# mbedshield041.net
KiCad netlist of a schematic drawn in EAGLE
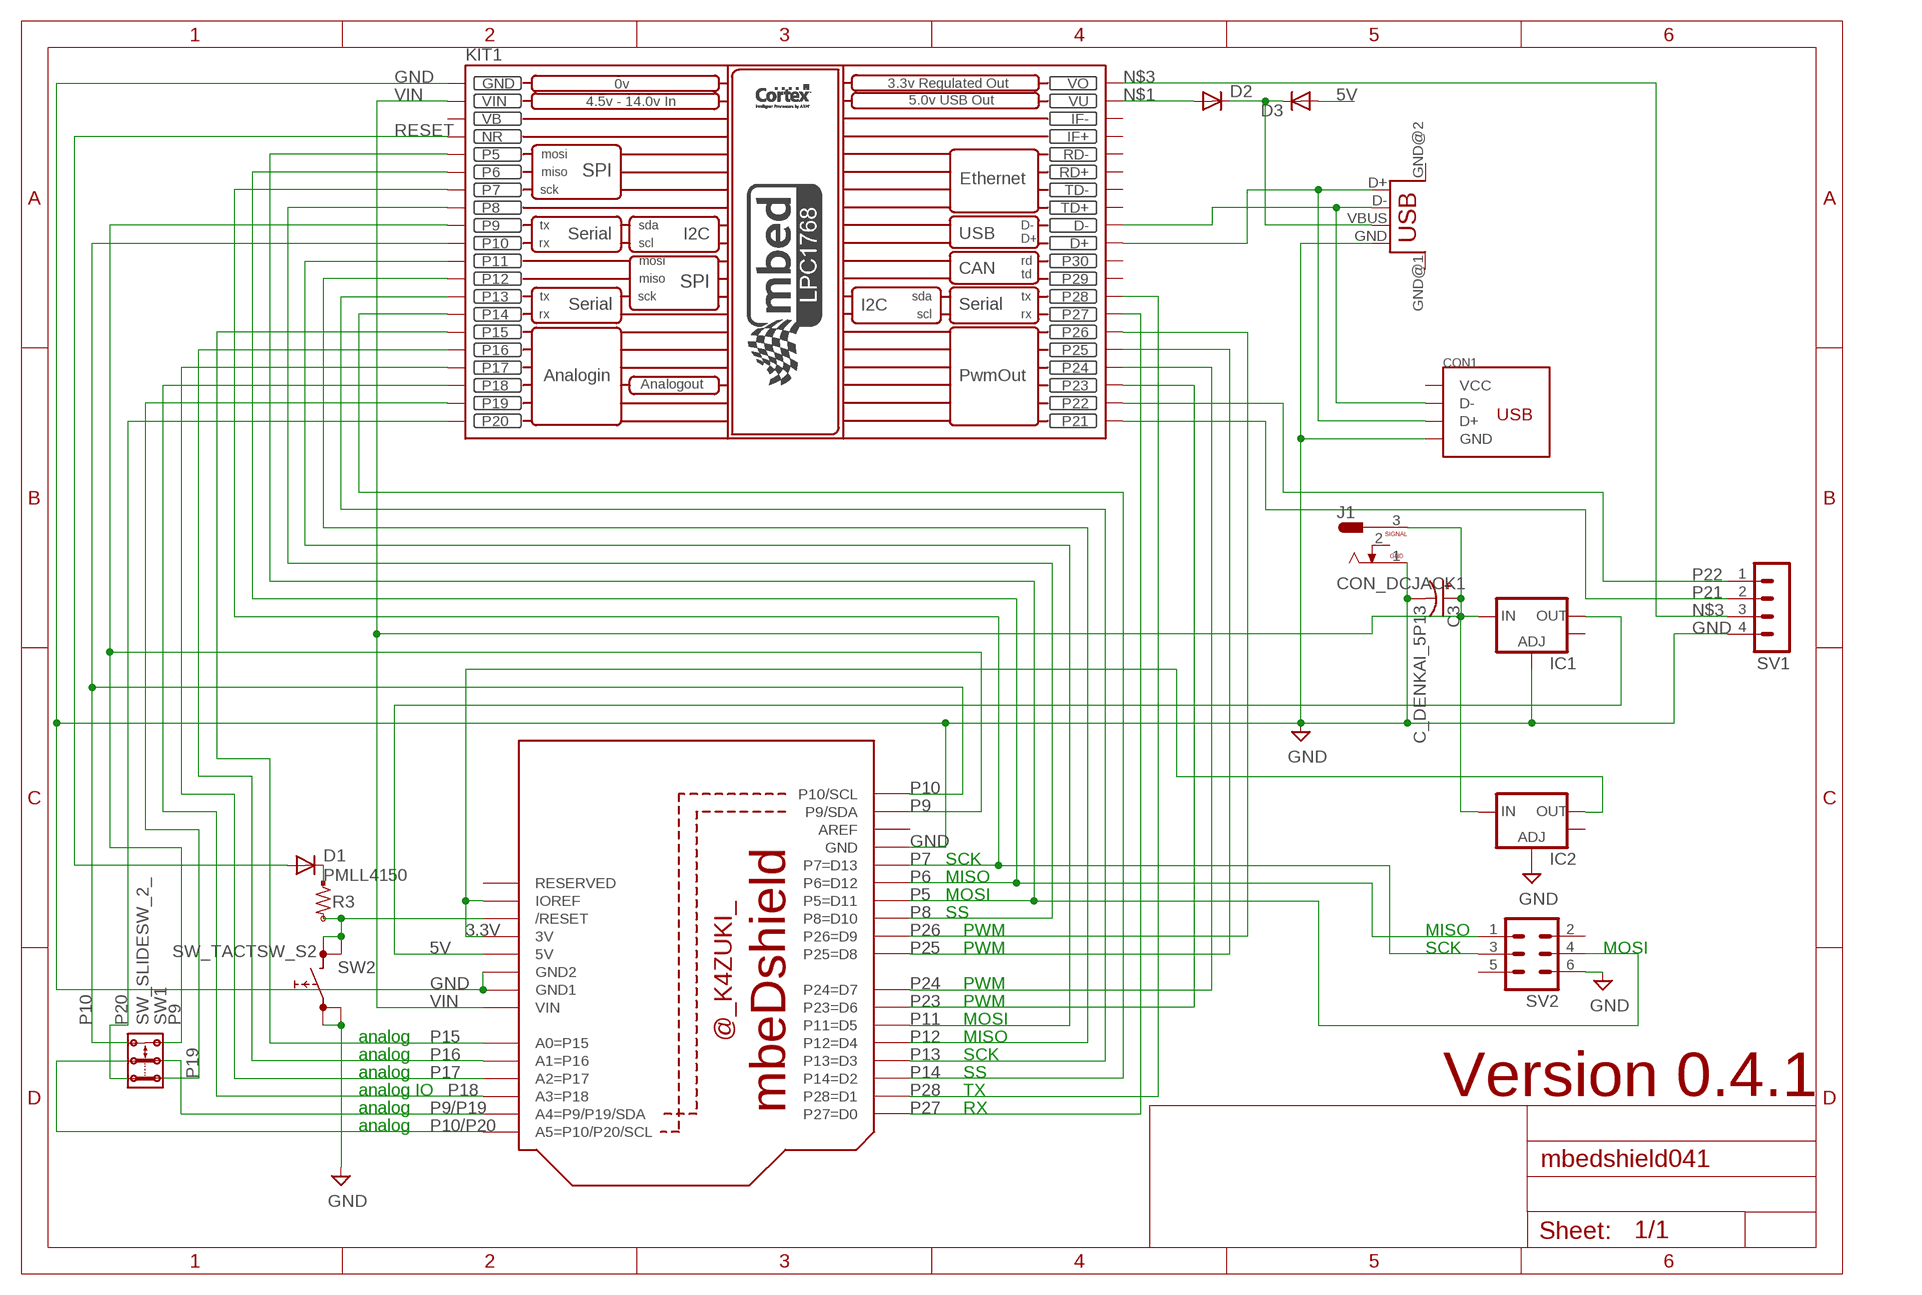
[diagram p0: schematic, sheet 1]

(export (version "E")
  (design (tool "Eeschema 10.0.6"))
  (components
    (comp (ref "C3")
      (value "C_DENKAI_5P13")
      (footprint "eagle-import:153CLV-1014")
      (libsource (lib "eagle-import") (part "CPOL-US153CLV-1014"))
    )
    (comp (ref "CON1")
      (value "CON_USB")
      (footprint "eagle-import:CON_USB_MINIB_AKI")
      (libsource (lib "eagle-import") (part "CON_USB"))
    )
    (comp (ref "D1")
      (value "PMLL4150")
      (footprint "eagle-import:SOD80C")
      (libsource (lib "eagle-import") (part "PMLL4150"))
    )
    (comp (ref "D2")
      (value "PMLL4150")
      (footprint "eagle-import:SOD80C")
      (libsource (lib "eagle-import") (part "PMLL4150"))
    )
    (comp (ref "D3")
      (value "PMLL4150")
      (footprint "eagle-import:SOD80C")
      (libsource (lib "eagle-import") (part "PMLL4150"))
    )
    (comp (ref "IC1")
      (value "V_REG_LM1117SOT223")
      (footprint "eagle-import:SOT223")
      (libsource (lib "eagle-import") (part "V_REG_LM1117SOT223"))
    )
    (comp (ref "IC2")
      (value "V_REG_LM1117SOT223")
      (footprint "eagle-import:SOT223")
      (libsource (lib "eagle-import") (part "V_REG_LM1117SOT223"))
    )
    (comp (ref "J1")
      (value "CON_DCJACK1")
      (footprint "eagle-import:CON_DCJACK")
      (libsource (lib "eagle-import") (part "CON_DCJACK1"))
    )
    (comp (ref "KIT1")
      (value "MBED_NXP_LPC1768")
      (footprint "eagle-import:MBED-KIT")
      (libsource (lib "eagle-import") (part "MBED_NXP_LPC1768"))
    )
    (comp (ref "R3")
      (value "R_US_PAD_VIA_2125")
      (footprint "eagle-import:R_2125_PADVIA")
      (libsource (lib "eagle-import") (part "R_US_PAD_VIA_2125"))
    )
    (comp (ref "SV1")
      (value "MA04-1")
      (footprint "eagle-import:MA04-1")
      (libsource (lib "eagle-import") (part "MA04-1"))
    )
    (comp (ref "SV2")
      (value "MA03-2")
      (footprint "eagle-import:MA03-2")
      (libsource (lib "eagle-import") (part "MA03-2"))
    )
    (comp (ref "SW1")
      (value "SW_SLIDESW_2_")
      (footprint "eagle-import:SW_SLIDE_2X2_1")
      (libsource (lib "eagle-import") (part "SW_SLIDESW_2_"))
    )
    (comp (ref "SW2")
      (value "SW_TACTSW_S2")
      (footprint "eagle-import:SW_TACTSW_B3F-10XX")
      (libsource (lib "eagle-import") (part "SW_TACTSW_S2"))
    )
    (comp (ref "U$1")
      (value "BOARD_MBEDSHIELD")
      (footprint "eagle-import:BOARD_MBEDSHIOELD")
      (libsource (lib "eagle-import") (part "BOARD_MBEDSHIELD"))
    )
    (comp (ref "USB")
      (value "USB")
      (footprint "eagle-import:USB-FEMALE-A-PTH")
      (libsource (lib "eagle-import") (part "USB"))
    )
  )
  (nets
    (net (code "1") (name "/3.3V") (class "Default")
      (node (ref "IC2") (pin "2") (pinfunction "OUT_2") (pintype "output"))
      (node (ref "U$1") (pin "3V") (pinfunction "3V_3V") (pintype "power_in"))
      (node (ref "U$1") (pin "IOREF") (pinfunction "IOREF_IOREF") (pintype "output"))
    )
    (net (code "2") (name "/5V") (class "Default")
      (node (ref "D3") (pin "A") (pinfunction "A_A") (pintype "passive"))
      (node (ref "IC1") (pin "2") (pinfunction "OUT_2") (pintype "output"))
      (node (ref "U$1") (pin "5V") (pinfunction "5V_5V") (pintype "power_in"))
    )
    (net (code "3") (name "/N$1") (class "Default")
      (node (ref "D2") (pin "A") (pinfunction "A_A") (pintype "passive"))
      (node (ref "KIT1") (pin "VU") (pinfunction "VU_VU") (pintype "power_in"))
    )
    (net (code "4") (name "/N$3") (class "Default")
      (node (ref "KIT1") (pin "VOUT") (pinfunction "VO_VOUT") (pintype "power_in"))
      (node (ref "SV1") (pin "3") (pinfunction "3_3") (pintype "passive"))
    )
    (net (code "5") (name "/P5") (class "Default")
      (node (ref "KIT1") (pin "P$5") (pinfunction "P5_P$5") (pintype "bidirectional"))
      (node (ref "SV2") (pin "4") (pinfunction "4_4") (pintype "passive"))
      (node (ref "U$1") (pin "D11") (pinfunction "P5=D11_D11") (pintype "bidirectional"))
    )
    (net (code "6") (name "/P6") (class "Default")
      (node (ref "KIT1") (pin "P$6") (pinfunction "P6_P$6") (pintype "bidirectional"))
      (node (ref "SV2") (pin "1") (pinfunction "1_1") (pintype "passive"))
      (node (ref "U$1") (pin "D12") (pinfunction "P6=D12_D12") (pintype "bidirectional"))
    )
    (net (code "7") (name "/P7") (class "Default")
      (node (ref "KIT1") (pin "P$7") (pinfunction "P7_P$7") (pintype "bidirectional"))
      (node (ref "SV2") (pin "3") (pinfunction "3_3") (pintype "passive"))
      (node (ref "U$1") (pin "D13") (pinfunction "P7=D13_D13") (pintype "bidirectional"))
    )
    (net (code "8") (name "/P8") (class "Default")
      (node (ref "KIT1") (pin "P$8") (pinfunction "P8_P$8") (pintype "bidirectional"))
      (node (ref "U$1") (pin "D10") (pinfunction "P8=D10_D10") (pintype "bidirectional"))
    )
    (net (code "9") (name "/P9") (class "Default")
      (node (ref "KIT1") (pin "P$9") (pinfunction "P9_P$9") (pintype "bidirectional"))
      (node (ref "SW1") (pin "2.1") (pinfunction "2.1_2.1") (pintype "passive"))
      (node (ref "U$1") (pin "SDA") (pinfunction "P9/SDA_SDA") (pintype "bidirectional"))
    )
    (net (code "10") (name "/P9{slash}P19") (class "Default")
      (node (ref "SW1") (pin "COM.1") (pinfunction "COM.1_COM.1") (pintype "passive"))
      (node (ref "U$1") (pin "A4") (pinfunction "A4=P9/P19/SDA_A4") (pintype "bidirectional"))
    )
    (net (code "11") (name "/P10") (class "Default")
      (node (ref "KIT1") (pin "P$10") (pinfunction "P10_P$10") (pintype "bidirectional"))
      (node (ref "SW1") (pin "2.2") (pinfunction "2.2_2.2") (pintype "passive"))
      (node (ref "U$1") (pin "SCL") (pinfunction "P10/SCL_SCL") (pintype "bidirectional"))
    )
    (net (code "12") (name "/P10{slash}P20") (class "Default")
      (node (ref "SW1") (pin "COM.2") (pinfunction "COM.2_COM.2") (pintype "passive"))
      (node (ref "U$1") (pin "A5") (pinfunction "A5=P10/P20/SCL_A5") (pintype "bidirectional"))
    )
    (net (code "13") (name "/P11") (class "Default")
      (node (ref "KIT1") (pin "P$11") (pinfunction "P11_P$11") (pintype "bidirectional"))
      (node (ref "U$1") (pin "D5") (pinfunction "P11=D5_D5") (pintype "bidirectional"))
    )
    (net (code "14") (name "/P12") (class "Default")
      (node (ref "KIT1") (pin "P$12") (pinfunction "P12_P$12") (pintype "bidirectional"))
      (node (ref "U$1") (pin "D4") (pinfunction "P12=D4_D4") (pintype "bidirectional"))
    )
    (net (code "15") (name "/P13") (class "Default")
      (node (ref "KIT1") (pin "P$13") (pinfunction "P13_P$13") (pintype "bidirectional"))
      (node (ref "U$1") (pin "D3") (pinfunction "P13=D3_D3") (pintype "bidirectional"))
    )
    (net (code "16") (name "/P14") (class "Default")
      (node (ref "KIT1") (pin "P$14") (pinfunction "P14_P$14") (pintype "bidirectional"))
      (node (ref "U$1") (pin "D2") (pinfunction "P14=D2_D2") (pintype "bidirectional"))
    )
    (net (code "17") (name "/P15") (class "Default")
      (node (ref "KIT1") (pin "P$15") (pinfunction "P15_P$15") (pintype "bidirectional"))
      (node (ref "U$1") (pin "A0") (pinfunction "A0=P15_A0") (pintype "bidirectional"))
    )
    (net (code "18") (name "/P16") (class "Default")
      (node (ref "KIT1") (pin "P$16") (pinfunction "P16_P$16") (pintype "bidirectional"))
      (node (ref "U$1") (pin "A1") (pinfunction "A1=P16_A1") (pintype "bidirectional"))
    )
    (net (code "19") (name "/P17") (class "Default")
      (node (ref "KIT1") (pin "P$17") (pinfunction "P17_P$17") (pintype "bidirectional"))
      (node (ref "U$1") (pin "A2") (pinfunction "A2=P17_A2") (pintype "bidirectional"))
    )
    (net (code "20") (name "/P18") (class "Default")
      (node (ref "KIT1") (pin "P$18") (pinfunction "P18_P$18") (pintype "bidirectional"))
      (node (ref "U$1") (pin "A3") (pinfunction "A3=P18_A3") (pintype "bidirectional"))
    )
    (net (code "21") (name "/P19") (class "Default")
      (node (ref "KIT1") (pin "P$19") (pinfunction "P19_P$19") (pintype "bidirectional"))
      (node (ref "SW1") (pin "1.1") (pinfunction "1.1_1.1") (pintype "passive"))
    )
    (net (code "22") (name "/P20") (class "Default")
      (node (ref "KIT1") (pin "P$20") (pinfunction "P20_P$20") (pintype "bidirectional"))
      (node (ref "SW1") (pin "1.2") (pinfunction "1.2_1.2") (pintype "passive"))
    )
    (net (code "23") (name "/P21") (class "Default")
      (node (ref "KIT1") (pin "P$21") (pinfunction "P21_P$21") (pintype "bidirectional"))
      (node (ref "SV1") (pin "2") (pinfunction "2_2") (pintype "passive"))
    )
    (net (code "24") (name "/P22") (class "Default")
      (node (ref "KIT1") (pin "P$22") (pinfunction "P22_P$22") (pintype "bidirectional"))
      (node (ref "SV1") (pin "1") (pinfunction "1_1") (pintype "passive"))
    )
    (net (code "25") (name "/P23") (class "Default")
      (node (ref "KIT1") (pin "P$23") (pinfunction "P23_P$23") (pintype "bidirectional"))
      (node (ref "U$1") (pin "D6") (pinfunction "P23=D6_D6") (pintype "bidirectional"))
    )
    (net (code "26") (name "/P24") (class "Default")
      (node (ref "KIT1") (pin "P$24") (pinfunction "P24_P$24") (pintype "bidirectional"))
      (node (ref "U$1") (pin "D7") (pinfunction "P24=D7_D7") (pintype "bidirectional"))
    )
    (net (code "27") (name "/P25") (class "Default")
      (node (ref "KIT1") (pin "P$25") (pinfunction "P25_P$25") (pintype "bidirectional"))
      (node (ref "U$1") (pin "D8") (pinfunction "P25=D8_D8") (pintype "bidirectional"))
    )
    (net (code "28") (name "/P26") (class "Default")
      (node (ref "KIT1") (pin "P$26") (pinfunction "P26_P$26") (pintype "bidirectional"))
      (node (ref "U$1") (pin "D9") (pinfunction "P26=D9_D9") (pintype "bidirectional"))
    )
    (net (code "29") (name "/P27") (class "Default")
      (node (ref "KIT1") (pin "P$27") (pinfunction "P27_P$27") (pintype "bidirectional"))
      (node (ref "U$1") (pin "D0") (pinfunction "P27=D0_D0") (pintype "bidirectional"))
    )
    (net (code "30") (name "/P28") (class "Default")
      (node (ref "KIT1") (pin "P$28") (pinfunction "P28_P$28") (pintype "bidirectional"))
      (node (ref "U$1") (pin "D1") (pinfunction "P28=D1_D1") (pintype "bidirectional"))
    )
    (net (code "31") (name "/RESET") (class "Default")
      (node (ref "D1") (pin "A") (pinfunction "A_A") (pintype "passive"))
      (node (ref "KIT1") (pin "NR") (pinfunction "NR_NR") (pintype "power_in"))
    )
    (net (code "32") (name "/VB") (class "Default")
      (node (ref "KIT1") (pin "VB") (pinfunction "VB_VB") (pintype "power_in"))
    )
    (net (code "33") (name "/VIN") (class "Default")
      (node (ref "C3") (pin "+") (pinfunction "+_+") (pintype "passive"))
      (node (ref "IC1") (pin "3") (pinfunction "IN_3") (pintype "input"))
      (node (ref "IC2") (pin "3") (pinfunction "IN_3") (pintype "input"))
      (node (ref "J1") (pin "3") (pinfunction "1_3") (pintype "passive"))
      (node (ref "KIT1") (pin "VIN") (pinfunction "VIN_VIN") (pintype "power_in"))
      (node (ref "U$1") (pin "VIN") (pinfunction "VIN_VIN") (pintype "power_in"))
    )
    (net (code "34") (name "GND") (class "Default")
      (node (ref "C3") (pin "-") (pinfunction "-_-") (pintype "passive"))
      (node (ref "CON1") (pin "GND") (pinfunction "GND_GND") (pintype "bidirectional"))
      (node (ref "IC1") (pin "1") (pinfunction "ADJ_1") (pintype "input"))
      (node (ref "IC2") (pin "1") (pinfunction "ADJ_1") (pintype "input"))
      (node (ref "J1") (pin "1") (pinfunction "3_1") (pintype "passive"))
      (node (ref "KIT1") (pin "GND") (pinfunction "GND_GND") (pintype "power_in"))
      (node (ref "SV1") (pin "4") (pinfunction "4_4") (pintype "passive"))
      (node (ref "SV2") (pin "6") (pinfunction "6_6") (pintype "passive"))
      (node (ref "SW2") (pin "1") (pinfunction "0_1") (pintype "passive"))
      (node (ref "SW2") (pin "2") (pinfunction "0_2") (pintype "passive"))
      (node (ref "U$1") (pin "GND") (pinfunction "GND_GND") (pintype "power_in"))
      (node (ref "U$1") (pin "GND1") (pinfunction "GND1_GND1") (pintype "power_in"))
      (node (ref "U$1") (pin "GND2") (pinfunction "GND2_GND2") (pintype "power_in"))
      (node (ref "USB") (pin "GND") (pinfunction "GND_GND") (pintype "bidirectional"))
    )
    (net (code "35") (name "Net-(CON1-PadD+)") (class "Default")
      (node (ref "CON1") (pin "D+") (pinfunction "D+_D+") (pintype "bidirectional"))
      (node (ref "KIT1") (pin "D+") (pinfunction "D+_D+") (pintype "bidirectional"))
      (node (ref "USB") (pin "D+") (pinfunction "D+_D+") (pintype "bidirectional"))
    )
    (net (code "36") (name "Net-(CON1-PadD-)") (class "Default")
      (node (ref "CON1") (pin "D-") (pinfunction "D-_D-") (pintype "bidirectional"))
      (node (ref "KIT1") (pin "D-") (pinfunction "D-_D-") (pintype "bidirectional"))
      (node (ref "USB") (pin "D-") (pinfunction "D-_D-") (pintype "bidirectional"))
    )
    (net (code "37") (name "Net-(D1-PadC)") (class "Default")
      (node (ref "D1") (pin "C") (pinfunction "C_C") (pintype "passive"))
      (node (ref "R3") (pin "PAD") (pinfunction "PAD_PAD") (pintype "passive"))
    )
    (net (code "38") (name "Net-(D2-PadC)") (class "Default")
      (node (ref "D2") (pin "C") (pinfunction "C_C") (pintype "passive"))
      (node (ref "D3") (pin "C") (pinfunction "C_C") (pintype "passive"))
      (node (ref "USB") (pin "VBUS") (pinfunction "VBUS_VBUS") (pintype "bidirectional"))
    )
    (net (code "39") (name "Net-(U$1-{slash}RESET)") (class "Default")
      (node (ref "R3") (pin "VIA") (pinfunction "VIA_VIA") (pintype "passive"))
      (node (ref "SW2") (pin "3") (pinfunction "1_3") (pintype "passive"))
      (node (ref "SW2") (pin "4") (pinfunction "1_4") (pintype "passive"))
      (node (ref "U$1") (pin "RESET") (pinfunction "/RESET_RESET") (pintype "bidirectional"))
    )
    (net (code "40") (name "unconnected-(CON1-VCC-PadVBUS)") (class "Default")
      (node (ref "CON1") (pin "VBUS") (pinfunction "VCC_VBUS") (pintype "bidirectional"))
    )
    (net (code "41") (name "unconnected-(IC1-OUT-Pad4)") (class "Default")
      (node (ref "IC1") (pin "4") (pinfunction "OUT_4") (pintype "output"))
    )
    (net (code "42") (name "unconnected-(IC2-OUT-Pad4)") (class "Default")
      (node (ref "IC2") (pin "4") (pinfunction "OUT_4") (pintype "output"))
    )
    (net (code "43") (name "unconnected-(J1-Pad2)") (class "Default")
      (node (ref "J1") (pin "2") (pinfunction "2_2") (pintype "passive"))
    )
    (net (code "44") (name "unconnected-(KIT1-P29-PadP$29)") (class "Default")
      (node (ref "KIT1") (pin "P$29") (pinfunction "P29_P$29") (pintype "bidirectional"))
    )
    (net (code "45") (name "unconnected-(KIT1-P30-PadP$30)") (class "Default")
      (node (ref "KIT1") (pin "P$30") (pinfunction "P30_P$30") (pintype "bidirectional"))
    )
    (net (code "46") (name "unconnected-(KIT1-PadIF+)") (class "Default")
      (node (ref "KIT1") (pin "IF+") (pinfunction "IF+_IF+") (pintype "bidirectional"))
    )
    (net (code "47") (name "unconnected-(KIT1-PadIF-)") (class "Default")
      (node (ref "KIT1") (pin "IF-") (pinfunction "IF-_IF-") (pintype "bidirectional"))
    )
    (net (code "48") (name "unconnected-(KIT1-PadRD+)") (class "Default")
      (node (ref "KIT1") (pin "RD+") (pinfunction "RD+_RD+") (pintype "bidirectional"))
    )
    (net (code "49") (name "unconnected-(KIT1-PadRD-)") (class "Default")
      (node (ref "KIT1") (pin "RD-") (pinfunction "RD-_RD-") (pintype "bidirectional"))
    )
    (net (code "50") (name "unconnected-(KIT1-PadTD+)") (class "Default")
      (node (ref "KIT1") (pin "TD+") (pinfunction "TD+_TD+") (pintype "bidirectional"))
    )
    (net (code "51") (name "unconnected-(KIT1-PadTD-)") (class "Default")
      (node (ref "KIT1") (pin "TD-") (pinfunction "TD-_TD-") (pintype "bidirectional"))
    )
    (net (code "52") (name "unconnected-(SV2-Pad2)") (class "Default")
      (node (ref "SV2") (pin "2") (pinfunction "2_2") (pintype "passive"))
    )
    (net (code "53") (name "unconnected-(SV2-Pad5)") (class "Default")
      (node (ref "SV2") (pin "5") (pinfunction "5_5") (pintype "passive"))
    )
    (net (code "54") (name "unconnected-(U$1-PadAREF)") (class "Default")
      (node (ref "U$1") (pin "AREF") (pinfunction "AREF_AREF") (pintype "bidirectional"))
    )
    (net (code "55") (name "unconnected-(U$1-PadRESERVED)") (class "Default")
      (node (ref "U$1") (pin "RESERVED") (pinfunction "RESERVED_RESERVED") (pintype "no_connect"))
    )
    (net (code "56") (name "unconnected-(USB-GND-PadGND@1)") (class "Default")
      (node (ref "USB") (pin "GND@1") (pinfunction "GND_GND@1") (pintype "bidirectional"))
    )
    (net (code "57") (name "unconnected-(USB-GND-PadGND@2)") (class "Default")
      (node (ref "USB") (pin "GND@2") (pinfunction "GND_GND@2") (pintype "bidirectional"))
    )
  )
)
